# vDAC1.net
KiCad netlist of a schematic drawn in Altium Designer
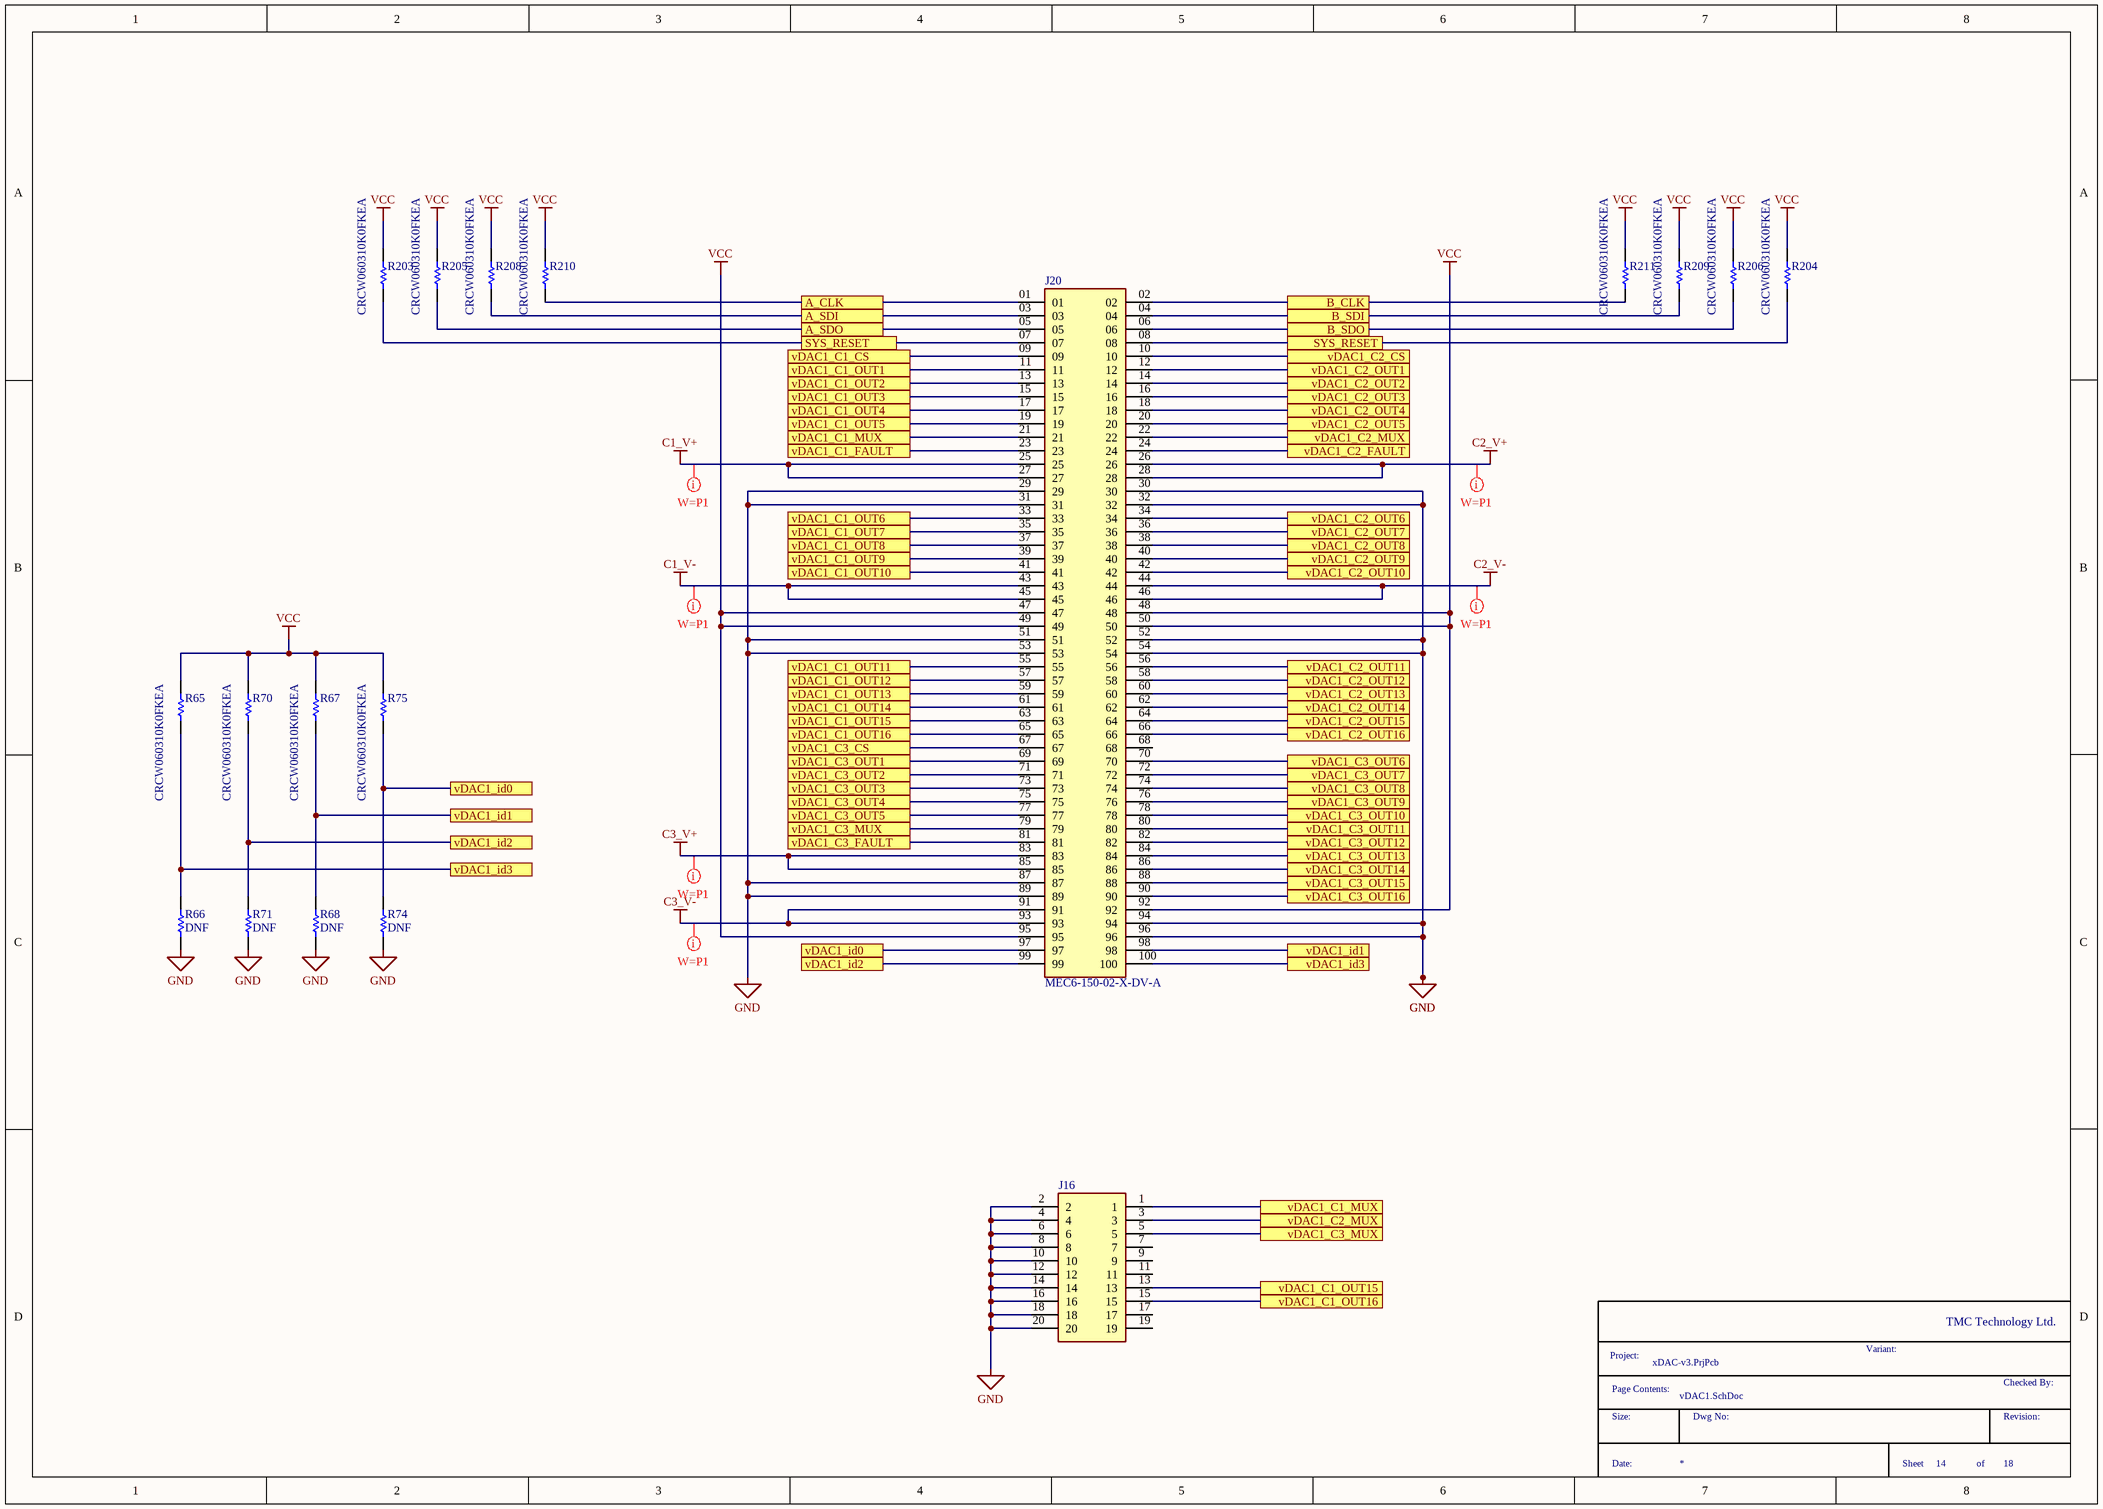
[diagram p0: vDAC1.SchDoc]

(export (version "E")
  (design (tool "Eeschema 10.0.6"))
  (components
    (comp (ref "J16")
      (value "~")
      (footprint "xDAC_Carrier:HDRV20W40P127_2X10_1270X340X550P")
      (description "Connector")
      (fields (field (name "MANUFACTURER_PART_NUMBER") "20021111-00020T4LF"))
      (libsource (lib "xDAC_Carrier") (part "20021111-00020T4LF"))
    )
    (comp (ref "J20")
      (value "MEC6-150-02-X-DV-A")
      (footprint "SAMTEC_MEC6-150-02-X-DV-A")
      (fields (field (name "MF") "Samtec"))
      (libsource (lib "xDAC_Carrier") (part "MEC6-150-02-X-DV-A"))
    )
    (comp (ref "R65")
      (value "CRCW060310K0FKEA")
      (footprint "RESC1609X50X30NL8T20")
      (description "Chip Resistor, 10 KOhm, +/- 1%, 100 mW, -55 to 155 degC, 0603 (1608 Metric), RoHS, Tape and Reel")
      (fields (field (name "MANUFACTURER") "Vishay"))
      (libsource (lib "xDAC_Carrier") (part "CMP-1666-00005-4"))
    )
    (comp (ref "R66")
      (value "DNF")
      (footprint "RESC1609X50X30NL8T20")
      (description "Chip Resistor, 0 Ohm, Jumper, 100 mW, -55 to 155 degC, 0603 (1608 Metric), RoHS, Tape and Reel")
      (fields
        (field (name "MANUFACTURER") "Vishay")
        (field (name "MANUFACTURER PART NUMBER") "CRCW0603-0000Z0EA")
      )
      (libsource (lib "xDAC_Carrier") (part "CMP-2000-03816-5"))
    )
    (comp (ref "R67")
      (value "CRCW060310K0FKEA")
      (footprint "RESC1609X50X30NL8T20")
      (description "Chip Resistor, 10 KOhm, +/- 1%, 100 mW, -55 to 155 degC, 0603 (1608 Metric), RoHS, Tape and Reel")
      (fields (field (name "MANUFACTURER") "Vishay"))
      (libsource (lib "xDAC_Carrier") (part "CMP-1666-00005-4"))
    )
    (comp (ref "R68")
      (value "DNF")
      (footprint "RESC1609X50X30NL8T20")
      (description "Chip Resistor, 0 Ohm, Jumper, 100 mW, -55 to 155 degC, 0603 (1608 Metric), RoHS, Tape and Reel")
      (fields
        (field (name "MANUFACTURER") "Vishay")
        (field (name "MANUFACTURER PART NUMBER") "CRCW0603-0000Z0EA")
      )
      (libsource (lib "xDAC_Carrier") (part "CMP-2000-03816-5"))
    )
    (comp (ref "R70")
      (value "CRCW060310K0FKEA")
      (footprint "RESC1609X50X30NL8T20")
      (description "Chip Resistor, 10 KOhm, +/- 1%, 100 mW, -55 to 155 degC, 0603 (1608 Metric), RoHS, Tape and Reel")
      (fields (field (name "MANUFACTURER") "Vishay"))
      (libsource (lib "xDAC_Carrier") (part "CMP-1666-00005-4"))
    )
    (comp (ref "R71")
      (value "DNF")
      (footprint "RESC1609X50X30NL8T20")
      (description "Chip Resistor, 0 Ohm, Jumper, 100 mW, -55 to 155 degC, 0603 (1608 Metric), RoHS, Tape and Reel")
      (fields
        (field (name "MANUFACTURER") "Vishay")
        (field (name "MANUFACTURER PART NUMBER") "CRCW0603-0000Z0EA")
      )
      (libsource (lib "xDAC_Carrier") (part "CMP-2000-03816-5"))
    )
    (comp (ref "R74")
      (value "DNF")
      (footprint "RESC1609X50X30NL8T20")
      (description "Chip Resistor, 0 Ohm, Jumper, 100 mW, -55 to 155 degC, 0603 (1608 Metric), RoHS, Tape and Reel")
      (fields
        (field (name "MANUFACTURER") "Vishay")
        (field (name "MANUFACTURER PART NUMBER") "CRCW0603-0000Z0EA")
      )
      (libsource (lib "xDAC_Carrier") (part "CMP-2000-03816-5"))
    )
    (comp (ref "R75")
      (value "CRCW060310K0FKEA")
      (footprint "RESC1609X50X30NL8T20")
      (description "Chip Resistor, 10 KOhm, +/- 1%, 100 mW, -55 to 155 degC, 0603 (1608 Metric), RoHS, Tape and Reel")
      (fields (field (name "MANUFACTURER") "Vishay"))
      (libsource (lib "xDAC_Carrier") (part "CMP-1666-00005-4"))
    )
    (comp (ref "R203")
      (value "CRCW060310K0FKEA")
      (footprint "RESC1609X50X30NL8T20")
      (description "Chip Resistor, 10 KOhm, +/- 1%, 100 mW, -55 to 155 degC, 0603 (1608 Metric), RoHS, Tape and Reel")
      (fields (field (name "MANUFACTURER") "Vishay"))
      (libsource (lib "xDAC_Carrier") (part "CMP-1666-00005-4"))
    )
    (comp (ref "R204")
      (value "CRCW060310K0FKEA")
      (footprint "RESC1609X50X30NL8T20")
      (description "Chip Resistor, 10 KOhm, +/- 1%, 100 mW, -55 to 155 degC, 0603 (1608 Metric), RoHS, Tape and Reel")
      (fields (field (name "MANUFACTURER") "Vishay"))
      (libsource (lib "xDAC_Carrier") (part "CMP-1666-00005-4"))
    )
    (comp (ref "R205")
      (value "CRCW060310K0FKEA")
      (footprint "RESC1609X50X30NL8T20")
      (description "Chip Resistor, 10 KOhm, +/- 1%, 100 mW, -55 to 155 degC, 0603 (1608 Metric), RoHS, Tape and Reel")
      (fields (field (name "MANUFACTURER") "Vishay"))
      (libsource (lib "xDAC_Carrier") (part "CMP-1666-00005-4"))
    )
    (comp (ref "R206")
      (value "CRCW060310K0FKEA")
      (footprint "RESC1609X50X30NL8T20")
      (description "Chip Resistor, 10 KOhm, +/- 1%, 100 mW, -55 to 155 degC, 0603 (1608 Metric), RoHS, Tape and Reel")
      (fields (field (name "MANUFACTURER") "Vishay"))
      (libsource (lib "xDAC_Carrier") (part "CMP-1666-00005-4"))
    )
    (comp (ref "R208")
      (value "CRCW060310K0FKEA")
      (footprint "RESC1609X50X30NL8T20")
      (description "Chip Resistor, 10 KOhm, +/- 1%, 100 mW, -55 to 155 degC, 0603 (1608 Metric), RoHS, Tape and Reel")
      (fields (field (name "MANUFACTURER") "Vishay"))
      (libsource (lib "xDAC_Carrier") (part "CMP-1666-00005-4"))
    )
    (comp (ref "R209")
      (value "CRCW060310K0FKEA")
      (footprint "RESC1609X50X30NL8T20")
      (description "Chip Resistor, 10 KOhm, +/- 1%, 100 mW, -55 to 155 degC, 0603 (1608 Metric), RoHS, Tape and Reel")
      (fields (field (name "MANUFACTURER") "Vishay"))
      (libsource (lib "xDAC_Carrier") (part "CMP-1666-00005-4"))
    )
    (comp (ref "R210")
      (value "CRCW060310K0FKEA")
      (footprint "RESC1609X50X30NL8T20")
      (description "Chip Resistor, 10 KOhm, +/- 1%, 100 mW, -55 to 155 degC, 0603 (1608 Metric), RoHS, Tape and Reel")
      (fields (field (name "MANUFACTURER") "Vishay"))
      (libsource (lib "xDAC_Carrier") (part "CMP-1666-00005-4"))
    )
    (comp (ref "R211")
      (value "CRCW060310K0FKEA")
      (footprint "RESC1609X50X30NL8T20")
      (description "Chip Resistor, 10 KOhm, +/- 1%, 100 mW, -55 to 155 degC, 0603 (1608 Metric), RoHS, Tape and Reel")
      (fields (field (name "MANUFACTURER") "Vishay"))
      (libsource (lib "xDAC_Carrier") (part "CMP-1666-00005-4"))
    )
  )
  (nets
    (net (code "1") (name "/A_CLK") (class "Default")
      (node (ref "J20") (pin "01") (pinfunction "01_01") (pintype "passive"))
      (node (ref "R210") (pin "1") (pinfunction "1_1") (pintype "passive"))
    )
    (net (code "2") (name "/A_SDI") (class "Default")
      (node (ref "J20") (pin "03") (pinfunction "03_03") (pintype "passive"))
      (node (ref "R208") (pin "1") (pinfunction "1_1") (pintype "passive"))
    )
    (net (code "3") (name "/A_SDO") (class "Default")
      (node (ref "J20") (pin "05") (pinfunction "05_05") (pintype "passive"))
      (node (ref "R205") (pin "1") (pinfunction "1_1") (pintype "passive"))
    )
    (net (code "4") (name "/B_CLK") (class "Default")
      (node (ref "J20") (pin "02") (pinfunction "02_02") (pintype "passive"))
      (node (ref "R211") (pin "1") (pinfunction "1_1") (pintype "passive"))
    )
    (net (code "5") (name "/B_SDI") (class "Default")
      (node (ref "J20") (pin "04") (pinfunction "04_04") (pintype "passive"))
      (node (ref "R209") (pin "1") (pinfunction "1_1") (pintype "passive"))
    )
    (net (code "6") (name "/B_SDO") (class "Default")
      (node (ref "J20") (pin "06") (pinfunction "06_06") (pintype "passive"))
      (node (ref "R206") (pin "1") (pinfunction "1_1") (pintype "passive"))
    )
    (net (code "7") (name "/SYS_RESET") (class "Default")
      (node (ref "J20") (pin "07") (pinfunction "07_07") (pintype "passive"))
      (node (ref "J20") (pin "08") (pinfunction "08_08") (pintype "passive"))
      (node (ref "R203") (pin "1") (pinfunction "1_1") (pintype "passive"))
      (node (ref "R204") (pin "1") (pinfunction "1_1") (pintype "passive"))
    )
    (net (code "8") (name "/vDAC1_C1_CS") (class "Default")
      (node (ref "J20") (pin "09") (pinfunction "09_09") (pintype "passive"))
    )
    (net (code "9") (name "/vDAC1_C1_FAULT") (class "Default")
      (node (ref "J20") (pin "23") (pinfunction "23_23") (pintype "passive"))
    )
    (net (code "10") (name "/vDAC1_C1_MUX") (class "Default")
      (node (ref "J16") (pin "1") (pinfunction "1_1") (pintype "passive"))
      (node (ref "J20") (pin "21") (pinfunction "21_21") (pintype "passive"))
    )
    (net (code "11") (name "/vDAC1_C1_OUT1") (class "Default")
      (node (ref "J20") (pin "11") (pinfunction "11_11") (pintype "passive"))
    )
    (net (code "12") (name "/vDAC1_C1_OUT2") (class "Default")
      (node (ref "J20") (pin "13") (pinfunction "13_13") (pintype "passive"))
    )
    (net (code "13") (name "/vDAC1_C1_OUT3") (class "Default")
      (node (ref "J20") (pin "15") (pinfunction "15_15") (pintype "passive"))
    )
    (net (code "14") (name "/vDAC1_C1_OUT4") (class "Default")
      (node (ref "J20") (pin "17") (pinfunction "17_17") (pintype "passive"))
    )
    (net (code "15") (name "/vDAC1_C1_OUT5") (class "Default")
      (node (ref "J20") (pin "19") (pinfunction "19_19") (pintype "passive"))
    )
    (net (code "16") (name "/vDAC1_C1_OUT6") (class "Default")
      (node (ref "J20") (pin "33") (pinfunction "33_33") (pintype "passive"))
    )
    (net (code "17") (name "/vDAC1_C1_OUT7") (class "Default")
      (node (ref "J20") (pin "35") (pinfunction "35_35") (pintype "passive"))
    )
    (net (code "18") (name "/vDAC1_C1_OUT8") (class "Default")
      (node (ref "J20") (pin "37") (pinfunction "37_37") (pintype "passive"))
    )
    (net (code "19") (name "/vDAC1_C1_OUT9") (class "Default")
      (node (ref "J20") (pin "39") (pinfunction "39_39") (pintype "passive"))
    )
    (net (code "20") (name "/vDAC1_C1_OUT10") (class "Default")
      (node (ref "J20") (pin "41") (pinfunction "41_41") (pintype "passive"))
    )
    (net (code "21") (name "/vDAC1_C1_OUT11") (class "Default")
      (node (ref "J20") (pin "55") (pinfunction "55_55") (pintype "passive"))
    )
    (net (code "22") (name "/vDAC1_C1_OUT12") (class "Default")
      (node (ref "J20") (pin "57") (pinfunction "57_57") (pintype "passive"))
    )
    (net (code "23") (name "/vDAC1_C1_OUT13") (class "Default")
      (node (ref "J20") (pin "59") (pinfunction "59_59") (pintype "passive"))
    )
    (net (code "24") (name "/vDAC1_C1_OUT14") (class "Default")
      (node (ref "J20") (pin "61") (pinfunction "61_61") (pintype "passive"))
    )
    (net (code "25") (name "/vDAC1_C1_OUT15") (class "Default")
      (node (ref "J16") (pin "13") (pinfunction "13_13") (pintype "passive"))
      (node (ref "J20") (pin "63") (pinfunction "63_63") (pintype "passive"))
    )
    (net (code "26") (name "/vDAC1_C1_OUT16") (class "Default")
      (node (ref "J16") (pin "15") (pinfunction "15_15") (pintype "passive"))
      (node (ref "J20") (pin "65") (pinfunction "65_65") (pintype "passive"))
    )
    (net (code "27") (name "/vDAC1_C2_CS") (class "Default")
      (node (ref "J20") (pin "10") (pinfunction "10_10") (pintype "passive"))
    )
    (net (code "28") (name "/vDAC1_C2_FAULT") (class "Default")
      (node (ref "J20") (pin "24") (pinfunction "24_24") (pintype "passive"))
    )
    (net (code "29") (name "/vDAC1_C2_MUX") (class "Default")
      (node (ref "J16") (pin "3") (pinfunction "3_3") (pintype "passive"))
      (node (ref "J20") (pin "22") (pinfunction "22_22") (pintype "passive"))
    )
    (net (code "30") (name "/vDAC1_C2_OUT1") (class "Default")
      (node (ref "J20") (pin "12") (pinfunction "12_12") (pintype "passive"))
    )
    (net (code "31") (name "/vDAC1_C2_OUT2") (class "Default")
      (node (ref "J20") (pin "14") (pinfunction "14_14") (pintype "passive"))
    )
    (net (code "32") (name "/vDAC1_C2_OUT3") (class "Default")
      (node (ref "J20") (pin "16") (pinfunction "16_16") (pintype "passive"))
    )
    (net (code "33") (name "/vDAC1_C2_OUT4") (class "Default")
      (node (ref "J20") (pin "18") (pinfunction "18_18") (pintype "passive"))
    )
    (net (code "34") (name "/vDAC1_C2_OUT5") (class "Default")
      (node (ref "J20") (pin "20") (pinfunction "20_20") (pintype "passive"))
    )
    (net (code "35") (name "/vDAC1_C2_OUT6") (class "Default")
      (node (ref "J20") (pin "34") (pinfunction "34_34") (pintype "passive"))
    )
    (net (code "36") (name "/vDAC1_C2_OUT7") (class "Default")
      (node (ref "J20") (pin "36") (pinfunction "36_36") (pintype "passive"))
    )
    (net (code "37") (name "/vDAC1_C2_OUT8") (class "Default")
      (node (ref "J20") (pin "38") (pinfunction "38_38") (pintype "passive"))
    )
    (net (code "38") (name "/vDAC1_C2_OUT9") (class "Default")
      (node (ref "J20") (pin "40") (pinfunction "40_40") (pintype "passive"))
    )
    (net (code "39") (name "/vDAC1_C2_OUT10") (class "Default")
      (node (ref "J20") (pin "42") (pinfunction "42_42") (pintype "passive"))
    )
    (net (code "40") (name "/vDAC1_C2_OUT11") (class "Default")
      (node (ref "J20") (pin "56") (pinfunction "56_56") (pintype "passive"))
    )
    (net (code "41") (name "/vDAC1_C2_OUT12") (class "Default")
      (node (ref "J20") (pin "58") (pinfunction "58_58") (pintype "passive"))
    )
    (net (code "42") (name "/vDAC1_C2_OUT13") (class "Default")
      (node (ref "J20") (pin "60") (pinfunction "60_60") (pintype "passive"))
    )
    (net (code "43") (name "/vDAC1_C2_OUT14") (class "Default")
      (node (ref "J20") (pin "62") (pinfunction "62_62") (pintype "passive"))
    )
    (net (code "44") (name "/vDAC1_C2_OUT15") (class "Default")
      (node (ref "J20") (pin "64") (pinfunction "64_64") (pintype "passive"))
    )
    (net (code "45") (name "/vDAC1_C2_OUT16") (class "Default")
      (node (ref "J20") (pin "66") (pinfunction "66_66") (pintype "passive"))
    )
    (net (code "46") (name "/vDAC1_C3_CS") (class "Default")
      (node (ref "J20") (pin "67") (pinfunction "67_67") (pintype "passive"))
    )
    (net (code "47") (name "/vDAC1_C3_FAULT") (class "Default")
      (node (ref "J20") (pin "81") (pinfunction "81_81") (pintype "passive"))
    )
    (net (code "48") (name "/vDAC1_C3_MUX") (class "Default")
      (node (ref "J16") (pin "5") (pinfunction "5_5") (pintype "passive"))
      (node (ref "J20") (pin "79") (pinfunction "79_79") (pintype "passive"))
    )
    (net (code "49") (name "/vDAC1_C3_OUT1") (class "Default")
      (node (ref "J20") (pin "69") (pinfunction "69_69") (pintype "passive"))
    )
    (net (code "50") (name "/vDAC1_C3_OUT2") (class "Default")
      (node (ref "J20") (pin "71") (pinfunction "71_71") (pintype "passive"))
    )
    (net (code "51") (name "/vDAC1_C3_OUT3") (class "Default")
      (node (ref "J20") (pin "73") (pinfunction "73_73") (pintype "passive"))
    )
    (net (code "52") (name "/vDAC1_C3_OUT4") (class "Default")
      (node (ref "J20") (pin "75") (pinfunction "75_75") (pintype "passive"))
    )
    (net (code "53") (name "/vDAC1_C3_OUT5") (class "Default")
      (node (ref "J20") (pin "77") (pinfunction "77_77") (pintype "passive"))
    )
    (net (code "54") (name "/vDAC1_C3_OUT6") (class "Default")
      (node (ref "J20") (pin "70") (pinfunction "70_70") (pintype "passive"))
    )
    (net (code "55") (name "/vDAC1_C3_OUT7") (class "Default")
      (node (ref "J20") (pin "72") (pinfunction "72_72") (pintype "passive"))
    )
    (net (code "56") (name "/vDAC1_C3_OUT8") (class "Default")
      (node (ref "J20") (pin "74") (pinfunction "74_74") (pintype "passive"))
    )
    (net (code "57") (name "/vDAC1_C3_OUT9") (class "Default")
      (node (ref "J20") (pin "76") (pinfunction "76_76") (pintype "passive"))
    )
    (net (code "58") (name "/vDAC1_C3_OUT10") (class "Default")
      (node (ref "J20") (pin "78") (pinfunction "78_78") (pintype "passive"))
    )
    (net (code "59") (name "/vDAC1_C3_OUT11") (class "Default")
      (node (ref "J20") (pin "80") (pinfunction "80_80") (pintype "passive"))
    )
    (net (code "60") (name "/vDAC1_C3_OUT12") (class "Default")
      (node (ref "J20") (pin "82") (pinfunction "82_82") (pintype "passive"))
    )
    (net (code "61") (name "/vDAC1_C3_OUT13") (class "Default")
      (node (ref "J20") (pin "84") (pinfunction "84_84") (pintype "passive"))
    )
    (net (code "62") (name "/vDAC1_C3_OUT14") (class "Default")
      (node (ref "J20") (pin "86") (pinfunction "86_86") (pintype "passive"))
    )
    (net (code "63") (name "/vDAC1_C3_OUT15") (class "Default")
      (node (ref "J20") (pin "88") (pinfunction "88_88") (pintype "passive"))
    )
    (net (code "64") (name "/vDAC1_C3_OUT16") (class "Default")
      (node (ref "J20") (pin "90") (pinfunction "90_90") (pintype "passive"))
    )
    (net (code "65") (name "/vDAC1_id0") (class "Default")
      (node (ref "J20") (pin "97") (pinfunction "97_97") (pintype "passive"))
      (node (ref "R74") (pin "2") (pinfunction "2_2") (pintype "passive"))
      (node (ref "R75") (pin "1") (pinfunction "1_1") (pintype "passive"))
    )
    (net (code "66") (name "/vDAC1_id1") (class "Default")
      (node (ref "J20") (pin "98") (pinfunction "98_98") (pintype "passive"))
      (node (ref "R67") (pin "1") (pinfunction "1_1") (pintype "passive"))
      (node (ref "R68") (pin "2") (pinfunction "2_2") (pintype "passive"))
    )
    (net (code "67") (name "/vDAC1_id2") (class "Default")
      (node (ref "J20") (pin "99") (pinfunction "99_99") (pintype "passive"))
      (node (ref "R70") (pin "1") (pinfunction "1_1") (pintype "passive"))
      (node (ref "R71") (pin "2") (pinfunction "2_2") (pintype "passive"))
    )
    (net (code "68") (name "/vDAC1_id3") (class "Default")
      (node (ref "J20") (pin "100") (pinfunction "100_100") (pintype "passive"))
      (node (ref "R65") (pin "1") (pinfunction "1_1") (pintype "passive"))
      (node (ref "R66") (pin "2") (pinfunction "2_2") (pintype "passive"))
    )
    (net (code "69") (name "C1_V+") (class "Default")
      (node (ref "J20") (pin "25") (pinfunction "25_25") (pintype "passive"))
      (node (ref "J20") (pin "27") (pinfunction "27_27") (pintype "passive"))
    )
    (net (code "70") (name "C1_V-") (class "Default")
      (node (ref "J20") (pin "43") (pinfunction "43_43") (pintype "passive"))
      (node (ref "J20") (pin "45") (pinfunction "45_45") (pintype "passive"))
    )
    (net (code "71") (name "C2_V+") (class "Default")
      (node (ref "J20") (pin "26") (pinfunction "26_26") (pintype "passive"))
      (node (ref "J20") (pin "28") (pinfunction "28_28") (pintype "passive"))
    )
    (net (code "72") (name "C2_V-") (class "Default")
      (node (ref "J20") (pin "44") (pinfunction "44_44") (pintype "passive"))
      (node (ref "J20") (pin "46") (pinfunction "46_46") (pintype "passive"))
    )
    (net (code "73") (name "C3_V+") (class "Default")
      (node (ref "J20") (pin "83") (pinfunction "83_83") (pintype "passive"))
      (node (ref "J20") (pin "85") (pinfunction "85_85") (pintype "passive"))
    )
    (net (code "74") (name "C3_V-") (class "Default")
      (node (ref "J20") (pin "91") (pinfunction "91_91") (pintype "passive"))
      (node (ref "J20") (pin "93") (pinfunction "93_93") (pintype "passive"))
    )
    (net (code "75") (name "GND") (class "Default")
      (node (ref "J16") (pin "10") (pinfunction "10_10") (pintype "passive"))
      (node (ref "J16") (pin "12") (pinfunction "12_12") (pintype "passive"))
      (node (ref "J16") (pin "14") (pinfunction "14_14") (pintype "passive"))
      (node (ref "J16") (pin "16") (pinfunction "16_16") (pintype "passive"))
      (node (ref "J16") (pin "18") (pinfunction "18_18") (pintype "passive"))
      (node (ref "J16") (pin "2") (pinfunction "2_2") (pintype "passive"))
      (node (ref "J16") (pin "20") (pinfunction "20_20") (pintype "passive"))
      (node (ref "J16") (pin "4") (pinfunction "4_4") (pintype "passive"))
      (node (ref "J16") (pin "6") (pinfunction "6_6") (pintype "passive"))
      (node (ref "J16") (pin "8") (pinfunction "8_8") (pintype "passive"))
      (node (ref "J20") (pin "29") (pinfunction "29_29") (pintype "passive"))
      (node (ref "J20") (pin "30") (pinfunction "30_30") (pintype "passive"))
      (node (ref "J20") (pin "31") (pinfunction "31_31") (pintype "passive"))
      (node (ref "J20") (pin "32") (pinfunction "32_32") (pintype "passive"))
      (node (ref "J20") (pin "51") (pinfunction "51_51") (pintype "passive"))
      (node (ref "J20") (pin "52") (pinfunction "52_52") (pintype "passive"))
      (node (ref "J20") (pin "53") (pinfunction "53_53") (pintype "passive"))
      (node (ref "J20") (pin "54") (pinfunction "54_54") (pintype "passive"))
      (node (ref "J20") (pin "87") (pinfunction "87_87") (pintype "passive"))
      (node (ref "J20") (pin "89") (pinfunction "89_89") (pintype "passive"))
      (node (ref "J20") (pin "94") (pinfunction "94_94") (pintype "passive"))
      (node (ref "J20") (pin "96") (pinfunction "96_96") (pintype "passive"))
      (node (ref "R66") (pin "1") (pinfunction "1_1") (pintype "passive"))
      (node (ref "R68") (pin "1") (pinfunction "1_1") (pintype "passive"))
      (node (ref "R71") (pin "1") (pinfunction "1_1") (pintype "passive"))
      (node (ref "R74") (pin "1") (pinfunction "1_1") (pintype "passive"))
    )
    (net (code "76") (name "VCC") (class "Default")
      (node (ref "J20") (pin "47") (pinfunction "47_47") (pintype "passive"))
      (node (ref "J20") (pin "48") (pinfunction "48_48") (pintype "passive"))
      (node (ref "J20") (pin "49") (pinfunction "49_49") (pintype "passive"))
      (node (ref "J20") (pin "50") (pinfunction "50_50") (pintype "passive"))
      (node (ref "J20") (pin "92") (pinfunction "92_92") (pintype "passive"))
      (node (ref "J20") (pin "95") (pinfunction "95_95") (pintype "passive"))
      (node (ref "R203") (pin "2") (pinfunction "2_2") (pintype "passive"))
      (node (ref "R204") (pin "2") (pinfunction "2_2") (pintype "passive"))
      (node (ref "R205") (pin "2") (pinfunction "2_2") (pintype "passive"))
      (node (ref "R206") (pin "2") (pinfunction "2_2") (pintype "passive"))
      (node (ref "R208") (pin "2") (pinfunction "2_2") (pintype "passive"))
      (node (ref "R209") (pin "2") (pinfunction "2_2") (pintype "passive"))
      (node (ref "R210") (pin "2") (pinfunction "2_2") (pintype "passive"))
      (node (ref "R211") (pin "2") (pinfunction "2_2") (pintype "passive"))
      (node (ref "R65") (pin "2") (pinfunction "2_2") (pintype "passive"))
      (node (ref "R67") (pin "2") (pinfunction "2_2") (pintype "passive"))
      (node (ref "R70") (pin "2") (pinfunction "2_2") (pintype "passive"))
      (node (ref "R75") (pin "2") (pinfunction "2_2") (pintype "passive"))
    )
    (net (code "77") (name "unconnected-(J16-Pad7)") (class "Default")
      (node (ref "J16") (pin "7") (pinfunction "7_7") (pintype "passive"))
    )
    (net (code "78") (name "unconnected-(J16-Pad9)") (class "Default")
      (node (ref "J16") (pin "9") (pinfunction "9_9") (pintype "passive"))
    )
    (net (code "79") (name "unconnected-(J16-Pad11)") (class "Default")
      (node (ref "J16") (pin "11") (pinfunction "11_11") (pintype "passive"))
    )
    (net (code "80") (name "unconnected-(J16-Pad17)") (class "Default")
      (node (ref "J16") (pin "17") (pinfunction "17_17") (pintype "passive"))
    )
    (net (code "81") (name "unconnected-(J16-Pad19)") (class "Default")
      (node (ref "J16") (pin "19") (pinfunction "19_19") (pintype "passive"))
    )
    (net (code "82") (name "unconnected-(J20-Pad68)") (class "Default")
      (node (ref "J20") (pin "68") (pinfunction "68_68") (pintype "passive"))
    )
  )
)
